# LcsNodes-Smart-Turnout-Socket-B_00_01.net
KiCad netlist of a schematic drawn in EasyEDA
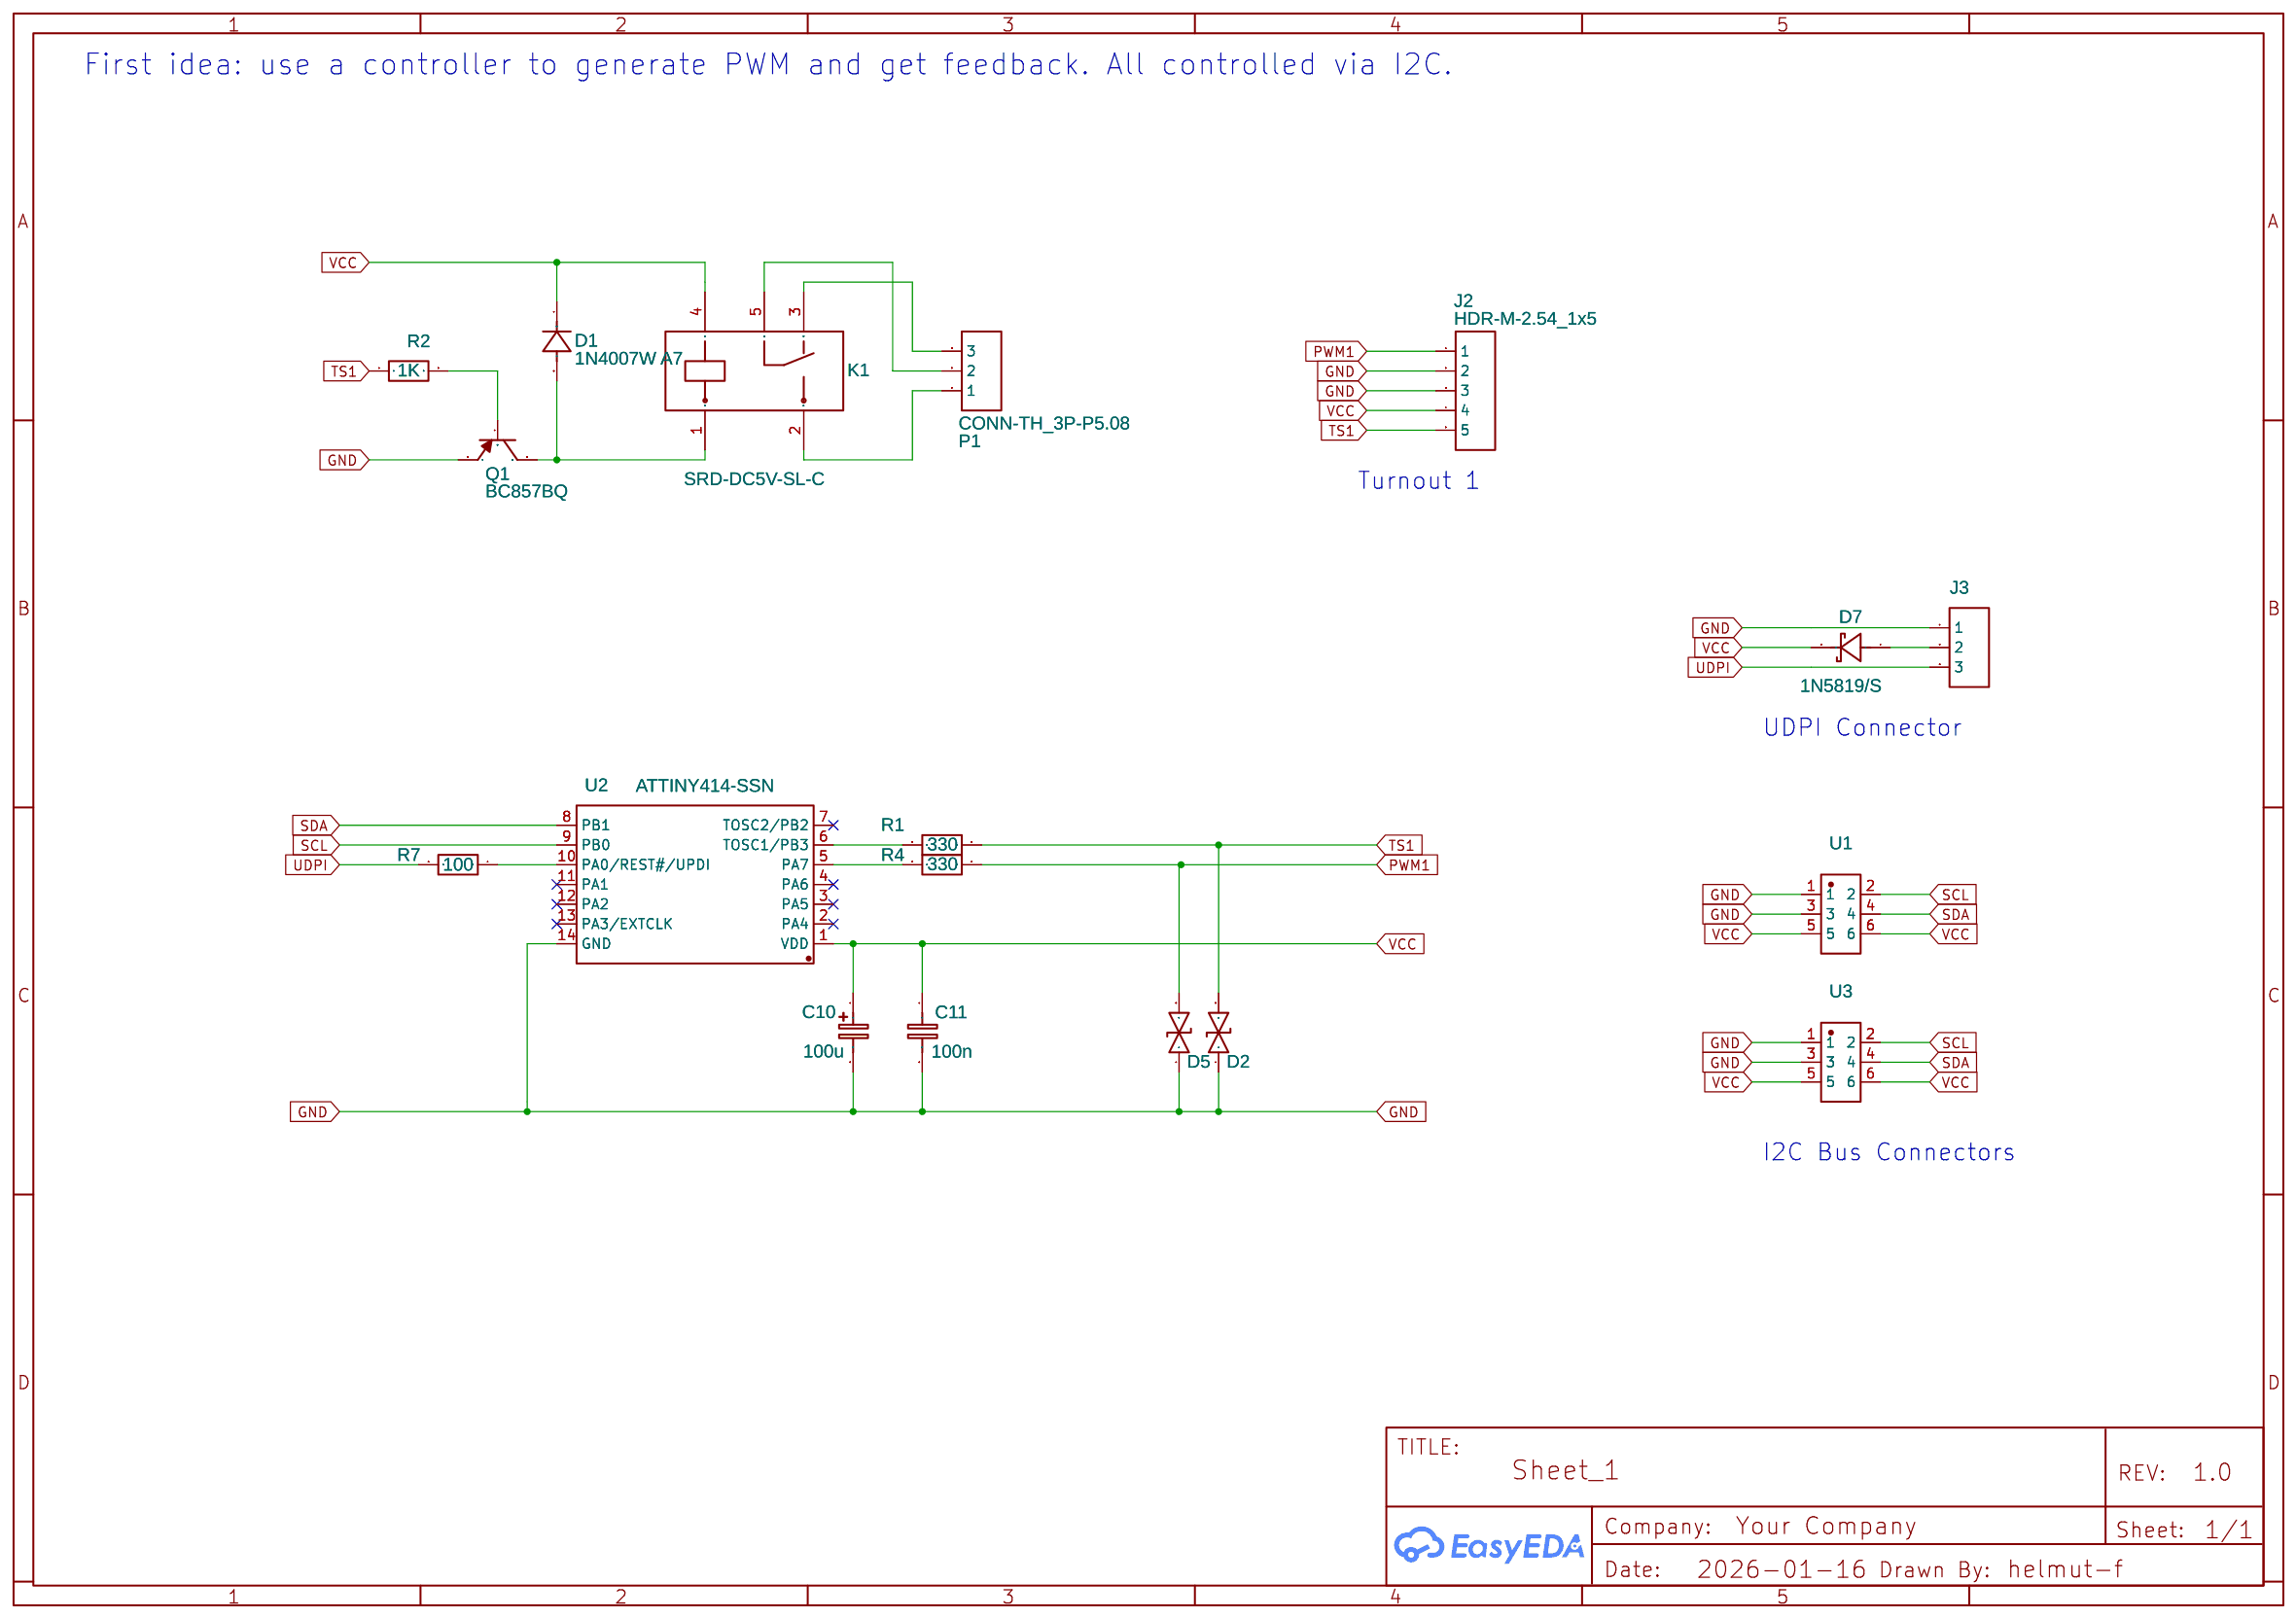
[diagram p0: schematic sheet]

(export (version "E")
  (design (tool "Eeschema 10.0.6"))
  (components
    (comp (ref "C10") (value "100u") (libsource (lib "") (part "CE_TH_D4.0×F1.5_EU")))
    (comp (ref "C11") (value "100n") (libsource (lib "") (part "C_0603_EU")))
    (comp (ref "D1")
      (value "1N4007W A7")
      (fields (field (name "Manufacturer") "JSMSEMI(杰盛微)"))
      (libsource (lib "") (part "1N4007W A7"))
    )
    (comp (ref "D2")
      (value "P4SMAJ5.0CA_R1_00001")
      (fields (field (name "Manufacturer") "PANJIT(强茂)"))
      (libsource (lib "") (part "P4SMAJ5.0CA_R1_00001"))
    )
    (comp (ref "D5")
      (value "P4SMAJ5.0CA_R1_00001")
      (fields (field (name "Manufacturer") "PANJIT(强茂)"))
      (libsource (lib "") (part "P4SMAJ5.0CA_R1_00001"))
    )
    (comp (ref "D7") (value "1N5819/S") (libsource (lib "") (part "1N5819/S")))
    (comp (ref "J2") (value "HDR-M-2.54_1x5") (libsource (lib "") (part "HDR-M-2.54_1x5")))
    (comp (ref "J3") (value "HDR-M-2.54_1x3") (libsource (lib "") (part "HDR-M-2.54_1x3")))
    (comp (ref "K1") (value "SRD-DC5V-SL-C") (libsource (lib "") (part "SRD-DC5V-SL-C")))
    (comp (ref "P1") (value "CONN-TH_3P-P5.08") (libsource (lib "") (part "CONN-TH_3P-P5.08")))
    (comp (ref "Q1")
      (value "BC857BQ")
      (fields (field (name "Manufacturer") "YANGJIE(扬杰)"))
      (libsource (lib "") (part "BC857BQ"))
    )
    (comp (ref "R1") (value "330") (libsource (lib "") (part "R_0805_EU_1")))
    (comp (ref "R2") (value "1K") (libsource (lib "") (part "R_0805_EU")))
    (comp (ref "R4") (value "330") (libsource (lib "") (part "R_0805_EU_1")))
    (comp (ref "R7") (value "100") (libsource (lib "") (part "R_0805_EU_1")))
    (comp (ref "U1") (value "RJ12MINIRJ45_6P6C") (libsource (lib "") (part "RJ12MINIRJ45_6P6C")))
    (comp (ref "U2")
      (value "ATTINY414-SSN")
      (fields (field (name "Manufacturer") "MICROCHIP(美国微芯)"))
      (libsource (lib "") (part "ATTINY414-SSN"))
    )
    (comp (ref "U3") (value "RJ12MINIRJ45_6P6C") (libsource (lib "") (part "RJ12MINIRJ45_6P6C")))
  )
  (nets
    (net (code "1") (name "GND") (class "Default")
      (node (ref "C10") (pin "2") (pinfunction "2_2") (pintype "unspecified"))
      (node (ref "C11") (pin "2") (pinfunction "2_2") (pintype "unspecified"))
      (node (ref "D2") (pin "1") (pinfunction "1_1") (pintype "unspecified"))
      (node (ref "D5") (pin "1") (pinfunction "1_1") (pintype "unspecified"))
      (node (ref "J2") (pin "2") (pinfunction "2_2") (pintype "unspecified"))
      (node (ref "J2") (pin "3") (pinfunction "3_3") (pintype "unspecified"))
      (node (ref "J3") (pin "1") (pinfunction "1_1") (pintype "input"))
      (node (ref "Q1") (pin "2") (pinfunction "E_2") (pintype "unspecified"))
      (node (ref "U1") (pin "1") (pinfunction "1_1") (pintype "unspecified"))
      (node (ref "U1") (pin "3") (pinfunction "3_3") (pintype "unspecified"))
      (node (ref "U2") (pin "14") (pinfunction "GND_14") (pintype "unspecified"))
      (node (ref "U3") (pin "1") (pinfunction "1_1") (pintype "unspecified"))
      (node (ref "U3") (pin "3") (pinfunction "3_3") (pintype "unspecified"))
    )
    (net (code "2") (name "Net-(D1-A)") (class "Default")
      (node (ref "D1") (pin "2") (pinfunction "A_2") (pintype "unspecified"))
      (node (ref "K1") (pin "1") (pinfunction "1_1") (pintype "input"))
      (node (ref "Q1") (pin "3") (pinfunction "C_3") (pintype "unspecified"))
    )
    (net (code "3") (name "Net-(D7-A)") (class "Default")
      (node (ref "D7") (pin "1") (pinfunction "A_1") (pintype "unspecified"))
      (node (ref "J3") (pin "2") (pinfunction "2_2") (pintype "input"))
    )
    (net (code "4") (name "Net-(K1-Pad2)") (class "Default")
      (node (ref "K1") (pin "2") (pinfunction "2_2") (pintype "input"))
      (node (ref "P1") (pin "1") (pinfunction "1_1") (pintype "unspecified"))
    )
    (net (code "5") (name "Net-(K1-Pad3)") (class "Default")
      (node (ref "K1") (pin "3") (pinfunction "3_3") (pintype "input"))
      (node (ref "P1") (pin "3") (pinfunction "3_3") (pintype "unspecified"))
    )
    (net (code "6") (name "Net-(K1-Pad5)") (class "Default")
      (node (ref "K1") (pin "5") (pinfunction "5_5") (pintype "input"))
      (node (ref "P1") (pin "2") (pinfunction "2_2") (pintype "unspecified"))
    )
    (net (code "7") (name "Net-(Q1-B)") (class "Default")
      (node (ref "Q1") (pin "1") (pinfunction "B_1") (pintype "unspecified"))
      (node (ref "R2") (pin "2") (pinfunction "2_2") (pintype "unspecified"))
    )
    (net (code "8") (name "Net-(U2-PA0{slash}REST#{slash}UPDI)") (class "Default")
      (node (ref "R7") (pin "1") (pinfunction "1_1") (pintype "unspecified"))
      (node (ref "U2") (pin "10") (pinfunction "PA0/REST#/UPDI_10") (pintype "unspecified"))
    )
    (net (code "9") (name "Net-(U2-PA7)") (class "Default")
      (node (ref "R4") (pin "2") (pinfunction "2_2") (pintype "unspecified"))
      (node (ref "U2") (pin "5") (pinfunction "PA7_5") (pintype "unspecified"))
    )
    (net (code "10") (name "Net-(U2-TOSC1{slash}PB3)") (class "Default")
      (node (ref "R1") (pin "2") (pinfunction "2_2") (pintype "unspecified"))
      (node (ref "U2") (pin "6") (pinfunction "TOSC1/PB3_6") (pintype "unspecified"))
    )
    (net (code "11") (name "PWM1") (class "Default")
      (node (ref "D5") (pin "2") (pinfunction "2_2") (pintype "unspecified"))
      (node (ref "J2") (pin "1") (pinfunction "1_1") (pintype "unspecified"))
      (node (ref "R4") (pin "1") (pinfunction "1_1") (pintype "unspecified"))
    )
    (net (code "12") (name "SCL") (class "Default")
      (node (ref "U1") (pin "2") (pinfunction "2_2") (pintype "unspecified"))
      (node (ref "U2") (pin "9") (pinfunction "PB0_9") (pintype "unspecified"))
      (node (ref "U3") (pin "2") (pinfunction "2_2") (pintype "unspecified"))
    )
    (net (code "13") (name "SDA") (class "Default")
      (node (ref "U1") (pin "4") (pinfunction "4_4") (pintype "unspecified"))
      (node (ref "U2") (pin "8") (pinfunction "PB1_8") (pintype "unspecified"))
      (node (ref "U3") (pin "4") (pinfunction "4_4") (pintype "unspecified"))
    )
    (net (code "14") (name "TS1") (class "Default")
      (node (ref "D2") (pin "2") (pinfunction "2_2") (pintype "unspecified"))
      (node (ref "J2") (pin "5") (pinfunction "5_5") (pintype "unspecified"))
      (node (ref "R1") (pin "1") (pinfunction "1_1") (pintype "unspecified"))
      (node (ref "R2") (pin "1") (pinfunction "1_1") (pintype "unspecified"))
    )
    (net (code "15") (name "UDPI") (class "Default")
      (node (ref "J3") (pin "3") (pinfunction "3_3") (pintype "input"))
      (node (ref "R7") (pin "2") (pinfunction "2_2") (pintype "unspecified"))
    )
    (net (code "16") (name "VCC") (class "Default")
      (node (ref "C10") (pin "1") (pinfunction "1_1") (pintype "unspecified"))
      (node (ref "C11") (pin "1") (pinfunction "1_1") (pintype "unspecified"))
      (node (ref "D1") (pin "1") (pinfunction "C_1") (pintype "unspecified"))
      (node (ref "D7") (pin "2") (pinfunction "K_2") (pintype "unspecified"))
      (node (ref "J2") (pin "4") (pinfunction "4_4") (pintype "unspecified"))
      (node (ref "K1") (pin "4") (pinfunction "4_4") (pintype "input"))
      (node (ref "U1") (pin "5") (pinfunction "5_5") (pintype "unspecified"))
      (node (ref "U1") (pin "6") (pinfunction "6_6") (pintype "unspecified"))
      (node (ref "U2") (pin "1") (pinfunction "VDD_1") (pintype "unspecified"))
      (node (ref "U3") (pin "5") (pinfunction "5_5") (pintype "unspecified"))
      (node (ref "U3") (pin "6") (pinfunction "6_6") (pintype "unspecified"))
    )
    (net (code "17") (name "unconnected-(U2-PA1-Pad11)") (class "Default")
      (node (ref "U2") (pin "11") (pinfunction "PA1_11") (pintype "unspecified+no_connect"))
    )
    (net (code "18") (name "unconnected-(U2-PA2-Pad12)") (class "Default")
      (node (ref "U2") (pin "12") (pinfunction "PA2_12") (pintype "unspecified+no_connect"))
    )
    (net (code "19") (name "unconnected-(U2-PA3{slash}EXTCLK-Pad13)") (class "Default")
      (node (ref "U2") (pin "13") (pinfunction "PA3/EXTCLK_13") (pintype "unspecified+no_connect"))
    )
    (net (code "20") (name "unconnected-(U2-PA4-Pad2)") (class "Default")
      (node (ref "U2") (pin "2") (pinfunction "PA4_2") (pintype "unspecified+no_connect"))
    )
    (net (code "21") (name "unconnected-(U2-PA5-Pad3)") (class "Default")
      (node (ref "U2") (pin "3") (pinfunction "PA5_3") (pintype "unspecified+no_connect"))
    )
    (net (code "22") (name "unconnected-(U2-PA6-Pad4)") (class "Default")
      (node (ref "U2") (pin "4") (pinfunction "PA6_4") (pintype "unspecified+no_connect"))
    )
    (net (code "23") (name "unconnected-(U2-TOSC2{slash}PB2-Pad7)") (class "Default")
      (node (ref "U2") (pin "7") (pinfunction "TOSC2/PB2_7") (pintype "unspecified+no_connect"))
    )
  )
)
